# ModBus.net
KiCad netlist of a schematic drawn in Altium Designer
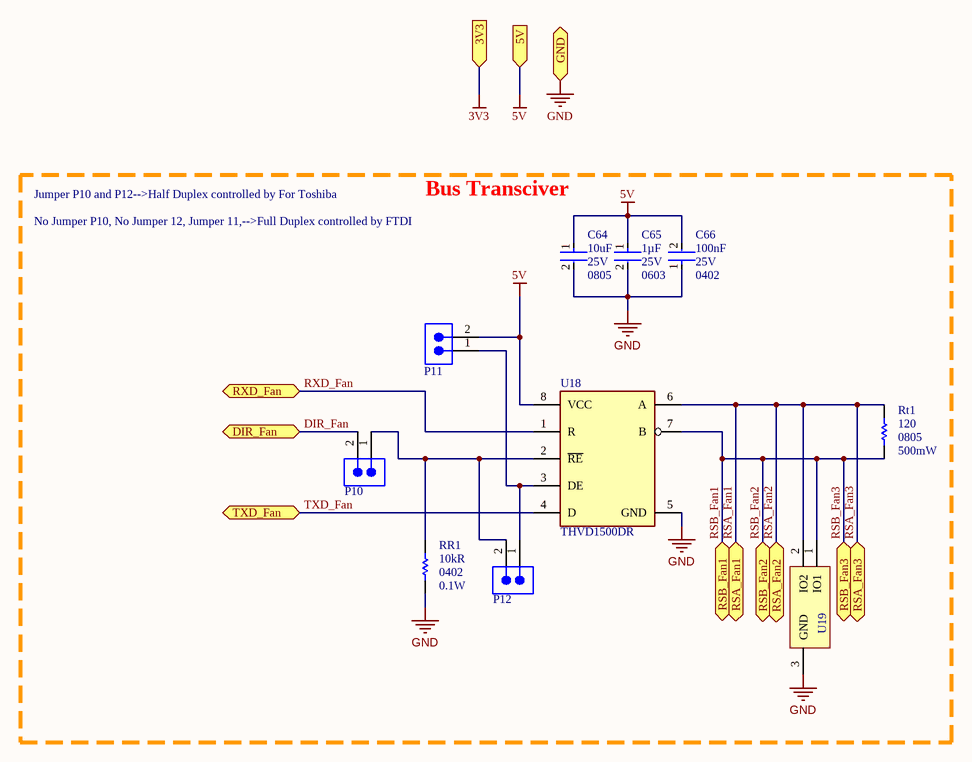
[diagram p0: ModBus.SchDoc]

(export (version "E")
  (design (tool "Eeschema 10.0.6"))
  (components
    (comp (ref "C64")
      (value "10uF")
      (footprint "FP-CL21-IPC_B")
      (description "CL21 Series 0805 10uF 25V ±10% Tolerance X5R Multilayer Ceramic Chip Capacitor")
      (fields
        (field (name "TOLERANCE") "10%")
        (field (name "CASE/PACKAGE") "0805")
        (field (name "VOLTAGE RATING") "25V")
        (field (name "Comment") "CL21A106KAFN3NE")
      )
      (libsource (lib "Altium Content Vault") (part "b4654b650e69147ec39a6b967a45e02"))
    )
    (comp (ref "C65")
      (value "1µF")
      (footprint "FP-0603-L_1_6_0_1-W_0_8_0-IPC_A")
      (fields
        (field (name "VOLTAGE RATING") "25V")
        (field (name "CASE/PACKAGE") "0603")
        (field (name "Comment") "TMK107B7105KA-T")
      )
      (libsource (lib "Digital Shovel") (part "02cd4be3c70576c341d710602a673aa"))
    )
    (comp (ref "C66")
      (value "100nF")
      (footprint "FP-CL830-IPC_A")
      (fields
        (field (name "VOLTAGE RATING") "25V")
        (field (name "CASE/PACKAGE") "0402")
        (field (name "Comment") "CL05B104KA5NNNC")
      )
      (libsource (lib "Digital Shovel") (part "b4654b650e69147ec39a6b967a45e02"))
    )
    (comp (ref "P10")
      (value "61300211121")
      (footprint "61300211121")
      (description "WR-PHD Pin Header, THT, Vertical, pitch 2.54mm, 1 Row, 2P")
      (fields (field (name "MANUFACTURER") "Wurth Elektronik"))
      (libsource (lib "Digital Shovel") (part "62000211121"))
    )
    (comp (ref "P11")
      (value "61300211121")
      (footprint "61300211121")
      (description "WR-PHD Pin Header, THT, Vertical, pitch 2.54mm, 1 Row, 2P")
      (fields (field (name "MANUFACTURER") "Wurth Elektronik"))
      (libsource (lib "Digital Shovel") (part "62000211121"))
    )
    (comp (ref "P12")
      (value "61300211121")
      (footprint "61300211121")
      (description "WR-PHD Pin Header, THT, Vertical, pitch 2.54mm, 1 Row, 2P")
      (fields (field (name "MANUFACTURER") "Wurth Elektronik"))
      (libsource (lib "Digital Shovel") (part "62000211121"))
    )
    (comp (ref "RR1")
      (value "10kR")
      (footprint "RESC1005X40X25LL10T10")
      (fields
        (field (name "PACKAGE") "0402")
        (field (name "POWER RATING") "0.1W")
        (field (name "Comment") "RK73H1ETTP1002F")
      )
      (libsource (lib "Digital Shovel") (part "RES"))
    )
    (comp (ref "Rt1")
      (value "120")
      (footprint "RESC2013X70X40NL20T20")
      (fields
        (field (name "POWER") "500mW")
        (field (name "TOLERANCE") "5%")
        (field (name "CASE/PACKAGE") "0805")
        (field (name "Comment") "ERJ-P06J121V")
      )
      (libsource (lib "Digital Shovel") (part "RES"))
    )
    (comp (ref "U18")
      (value "THVD1500DR")
      (footprint "FP-D0008B-IPC_A")
      (description "Line Transceiver, 1 Func, 1 Driver, 1 Rcvr, PDSO8")
      (libsource (lib "Digital Shovel") (part "0d76f8b61a7f9e0c6aec6fb1fff199e"))
    )
    (comp (ref "U19")
      (value "TPD2E007DCKR")
      (footprint "DCK0003A_M")
      (description "Trans Voltage Suppressor Diode, 13V V(RWM), Unidirectional, 4 Element, Silicon")
      (libsource (lib "Digital Shovel") (part "TI-TPD2E007-SC70_DCK-3"))
    )
  )
  (nets
    (net (code "1") (name "/DIR_Fan") (class "Default")
      (node (ref "P10") (pin "2") (pinfunction "2_2") (pintype "passive"))
    )
    (net (code "2") (name "/RSA_Fan1") (class "Default")
      (node (ref "Rt1") (pin "2") (pinfunction "2_2") (pintype "passive"))
      (node (ref "U18") (pin "6") (pinfunction "A_6") (pintype "passive"))
      (node (ref "U19") (pin "2") (pinfunction "IO2_2") (pintype "passive"))
    )
    (net (code "3") (name "/RSB_Fan1") (class "Default")
      (node (ref "Rt1") (pin "1") (pinfunction "1_1") (pintype "passive"))
      (node (ref "U18") (pin "7") (pinfunction "B_7") (pintype "passive"))
      (node (ref "U19") (pin "1") (pinfunction "IO1_1") (pintype "passive"))
    )
    (net (code "4") (name "/RXD_Fan") (class "Default")
      (node (ref "U18") (pin "1") (pinfunction "R_1") (pintype "passive"))
    )
    (net (code "5") (name "/TXD_Fan") (class "Default")
      (node (ref "U18") (pin "4") (pinfunction "D_4") (pintype "passive"))
    )
    (net (code "7") (name "5V") (class "Default")
      (node (ref "C64") (pin "1") (pinfunction "1_1") (pintype "passive"))
      (node (ref "C65") (pin "1") (pinfunction "1_1") (pintype "passive"))
      (node (ref "C66") (pin "2") (pinfunction "2_2") (pintype "passive"))
      (node (ref "P11") (pin "2") (pinfunction "2_2") (pintype "passive"))
      (node (ref "U18") (pin "8") (pinfunction "VCC_8") (pintype "passive"))
    )
    (net (code "8") (name "GND") (class "Default")
      (node (ref "C64") (pin "2") (pinfunction "2_2") (pintype "passive"))
      (node (ref "C65") (pin "2") (pinfunction "2_2") (pintype "passive"))
      (node (ref "C66") (pin "1") (pinfunction "1_1") (pintype "passive"))
      (node (ref "RR1") (pin "1") (pinfunction "1_1") (pintype "passive"))
      (node (ref "U18") (pin "5") (pinfunction "GND_5") (pintype "passive"))
      (node (ref "U19") (pin "3") (pinfunction "GND_3") (pintype "power_in"))
    )
    (net (code "9") (name "Net-(U18-DE)") (class "Default")
      (node (ref "P11") (pin "1") (pinfunction "1_1") (pintype "passive"))
      (node (ref "P12") (pin "1") (pinfunction "1_1") (pintype "passive"))
      (node (ref "U18") (pin "3") (pinfunction "DE_3") (pintype "passive"))
    )
    (net (code "10") (name "Net-(U18-~{RE})") (class "Default")
      (node (ref "P10") (pin "1") (pinfunction "1_1") (pintype "passive"))
      (node (ref "P12") (pin "2") (pinfunction "2_2") (pintype "passive"))
      (node (ref "RR1") (pin "2") (pinfunction "2_2") (pintype "passive"))
      (node (ref "U18") (pin "2") (pinfunction "~{RE}_2") (pintype "passive"))
    )
  )
)
